# BigDriver.net
KiCad netlist of a schematic drawn in Altium Designer
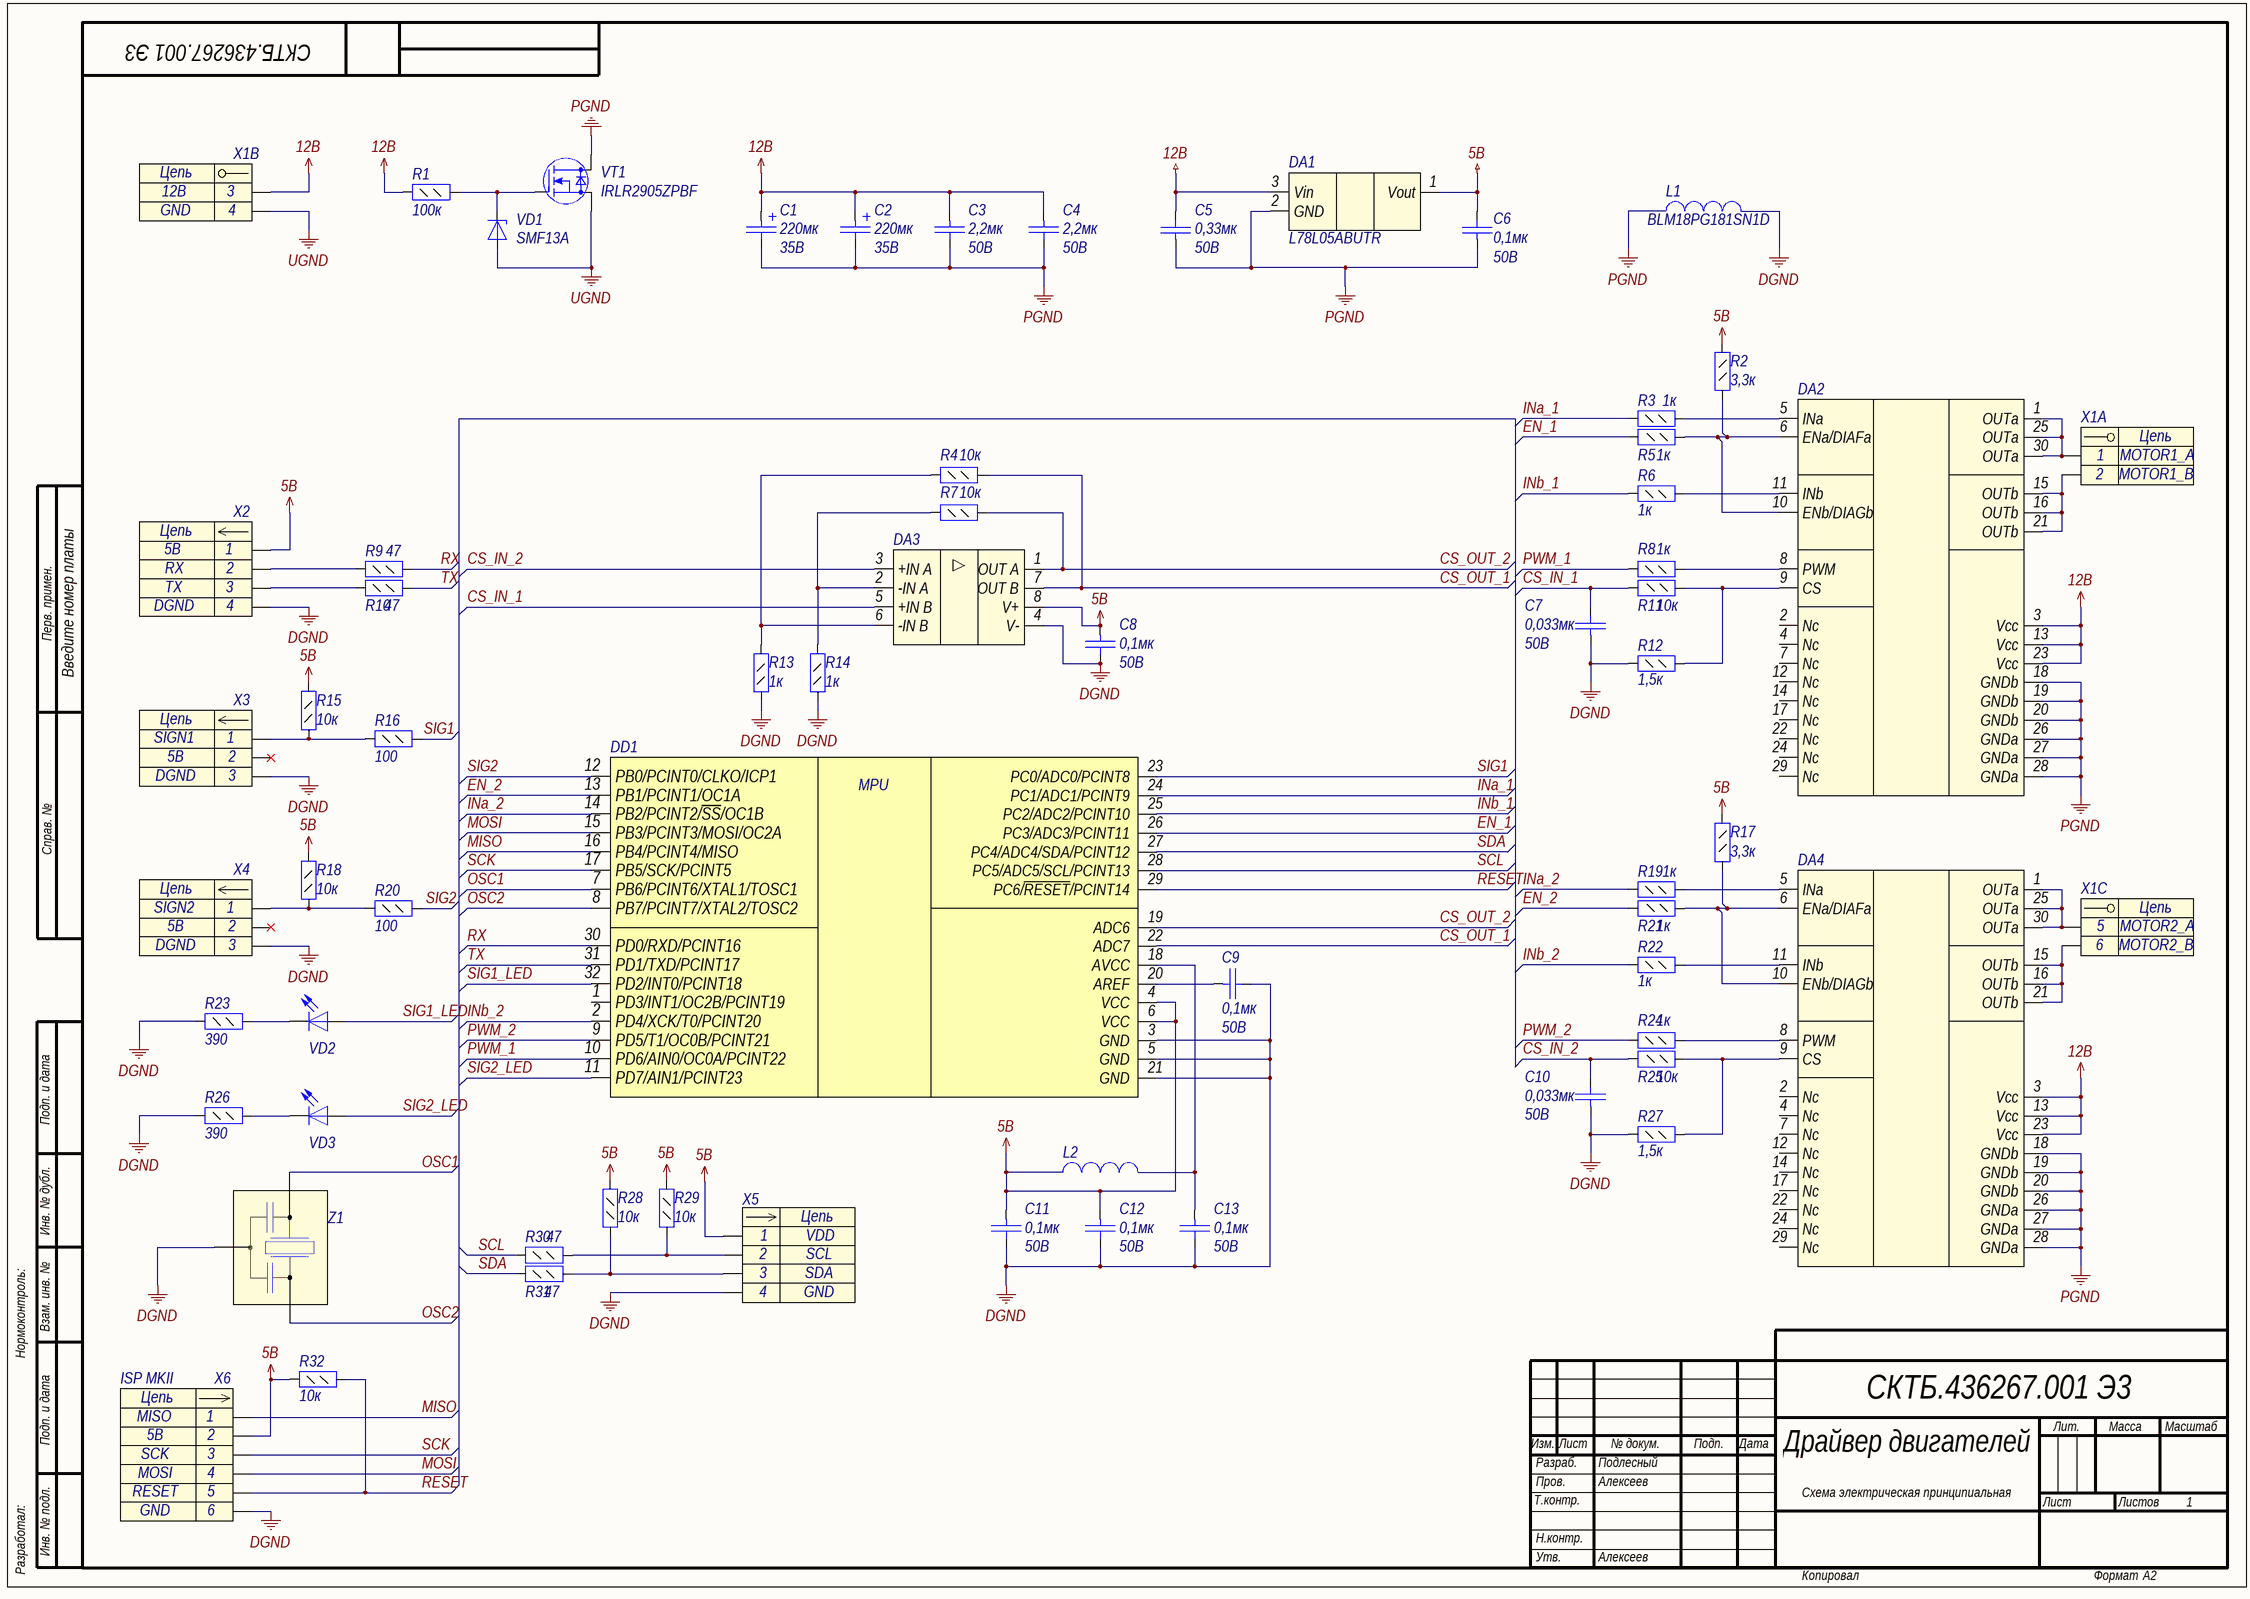
[diagram p0: BigDriver.SchDoc]

(export (version "E")
  (design (tool "Eeschema 10.0.6"))
  (components
    (comp (ref "C1")
      (value "220мк")
      (footprint "k50-35(8x11.5)_MIRROR")
      (description "Конденсатор полярный")
      (fields
        (field (name "VOLTAGE") "35В")
        (field (name "PART NUMBER") "TKR221M1VF11")
        (field (name "Comment") "Capacitor_pol")
      )
      (libsource (lib "MOP44") (part "Capacitor_pol"))
    )
    (comp (ref "C2")
      (value "220мк")
      (footprint "k50-35(8x11.5)_MIRROR")
      (description "Конденсатор полярный")
      (fields
        (field (name "VOLTAGE") "35В")
        (field (name "PART NUMBER") "TKR221M1VF11")
        (field (name "Comment") "Capacitor_pol")
      )
      (libsource (lib "MOP44") (part "Capacitor_pol"))
    )
    (comp (ref "C3")
      (value "2,2мк")
      (footprint "C1206")
      (description "Конденсатор")
      (fields
        (field (name "VOLTAGE") "50В")
        (field (name "PART NUMBER") "GRM31CR71H225KA88**L")
        (field (name "Comment") "Capacitor")
      )
      (libsource (lib "MOP44") (part "Capacitor"))
    )
    (comp (ref "C4")
      (value "2,2мк")
      (footprint "C1206")
      (description "Конденсатор")
      (fields
        (field (name "VOLTAGE") "50В")
        (field (name "PART NUMBER") "GRM31CR71H225KA88**L")
        (field (name "Comment") "Capacitor")
      )
      (libsource (lib "MOP44") (part "Capacitor"))
    )
    (comp (ref "C5")
      (value "0,33мк")
      (footprint "C1206")
      (description "Конденсатор")
      (fields
        (field (name "VOLTAGE") "50В")
        (field (name "PART NUMBER") "GRM319R71H334K")
        (field (name "Comment") "Capacitor")
      )
      (libsource (lib "MOP44") (part "Capacitor"))
    )
    (comp (ref "C6")
      (value "0,1мк")
      (footprint "C0805")
      (description "Конденсатор")
      (fields
        (field (name "VOLTAGE") "50В")
        (field (name "PART NUMBER") "GRM21BR71H104KA01L ")
        (field (name "Comment") "Capacitor")
      )
      (libsource (lib "MOP44") (part "Capacitor"))
    )
    (comp (ref "C7")
      (value "0,033мк")
      (footprint "C1206")
      (description "Конденсатор")
      (fields
        (field (name "VOLTAGE") "50В")
        (field (name "PART NUMBER") "GRM3195C1H333J")
        (field (name "Comment") "Capacitor")
      )
      (libsource (lib "MOP44") (part "Capacitor"))
    )
    (comp (ref "C8")
      (value "0,1мк")
      (footprint "C0805")
      (description "Конденсатор")
      (fields
        (field (name "VOLTAGE") "50В")
        (field (name "PART NUMBER") "GRM216R71H221K")
        (field (name "Comment") "Capacitor")
      )
      (libsource (lib "MOP44") (part "Capacitor"))
    )
    (comp (ref "C9")
      (value "0,1мк")
      (footprint "C0805")
      (description "Конденсатор")
      (fields
        (field (name "VOLTAGE") "50В")
        (field (name "PART NUMBER") "GRM216R71H221K")
        (field (name "Comment") "Capacitor")
      )
      (libsource (lib "MOP44") (part "Capacitor"))
    )
    (comp (ref "C10")
      (value "0,033мк")
      (footprint "C1206")
      (description "Конденсатор")
      (fields
        (field (name "VOLTAGE") "50В")
        (field (name "PART NUMBER") "GRM3195C1H333J")
        (field (name "Comment") "Capacitor")
      )
      (libsource (lib "MOP44") (part "Capacitor"))
    )
    (comp (ref "C11")
      (value "0,1мк")
      (footprint "C0805")
      (description "Конденсатор")
      (fields
        (field (name "VOLTAGE") "50В")
        (field (name "PART NUMBER") "GRM216R71H221K")
        (field (name "Comment") "Capacitor")
      )
      (libsource (lib "MOP44") (part "Capacitor"))
    )
    (comp (ref "C12")
      (value "0,1мк")
      (footprint "C0805")
      (description "Конденсатор")
      (fields
        (field (name "VOLTAGE") "50В")
        (field (name "PART NUMBER") "GRM216R71H221K")
        (field (name "Comment") "Capacitor")
      )
      (libsource (lib "MOP44") (part "Capacitor"))
    )
    (comp (ref "C13")
      (value "0,1мк")
      (footprint "C0805")
      (description "Конденсатор")
      (fields
        (field (name "VOLTAGE") "50В")
        (field (name "PART NUMBER") "GRM216R71H221K")
        (field (name "Comment") "Capacitor")
      )
      (libsource (lib "MOP44") (part "Capacitor"))
    )
    (comp (ref "DA1")
      (value "L78L05ABUTR")
      (footprint "SOT-89-3")
      (description "Cтабилизатор напряжения (+5В; 0.1А), 4%, (-40...+125C)")
      (fields (field (name "MANUFACTURER") "ST Microelectronics"))
      (libsource (lib "MOP44") (part "L78L05ABUTR"))
    )
    (comp (ref "DA2")
      (value "VNH2SP30-E")
      (footprint "MultiPowerSO-30")
      (description "Automotive fully integrated H-bridge motor driver")
      (libsource (lib "MOP44") (part "VNH2SP30-E"))
    )
    (comp (ref "DA3")
      (value "LMV358IDR")
      (footprint "SO8")
      (description "LOW-VOLTAGE RAIL-TO-RAIL OUTPUT OPERATIONAL AMPLIFIERS")
      (libsource (lib "MOP44") (part "LMV358IDR"))
    )
    (comp (ref "DA4")
      (value "VNH2SP30-E")
      (footprint "MultiPowerSO-30")
      (description "Automotive fully integrated H-bridge motor driver")
      (libsource (lib "MOP44") (part "VNH2SP30-E"))
    )
    (comp (ref "DD1")
      (value "ATmega328P-AU")
      (footprint "TQFP-32")
      (description "Микроконтроллер 8-Бит, picoPower, AVR, 20МГц, 32КБ Flash")
      (libsource (lib "MOP44") (part "ATmega328P-AU"))
    )
    (comp (ref "L1")
      (value "Inductor")
      (footprint "L0603")
      (description "EMI Suppression Filter")
      (fields (field (name "PART NUMBER") "BLM18PG181SN1D"))
      (libsource (lib "MOP44") (part "Inductor"))
    )
    (comp (ref "L2")
      (value "Inductor")
      (footprint "L0603")
      (description "EMI Suppression Filter")
      (fields (field (name "PART NUMBER") "BLM18PG181SN1D"))
      (libsource (lib "MOP44") (part "Inductor"))
    )
    (comp (ref "R1")
      (value "100к")
      (footprint "R0805")
      (description "Резистор")
      (fields (field (name "PART NUMBER") "RC0805FR-07100KL") (field (name "POWER") "0,125Вт"))
      (libsource (lib "") (part "Resistor_0,125Вт_1"))
    )
    (comp (ref "R2")
      (value "3,3к")
      (footprint "R0805")
      (description "Резистор")
      (fields (field (name "PART NUMBER") "RC0805FR-0710KL") (field (name "POWER") "0,125Вт"))
      (libsource (lib "") (part "Resistor_0,125Вт_2"))
    )
    (comp (ref "R3")
      (value "1к")
      (footprint "R0805")
      (description "Резистор")
      (fields (field (name "PART NUMBER") "RC0805FR-0710KL") (field (name "POWER") "0,125Вт"))
      (libsource (lib "") (part "Resistor_0,125Вт_1"))
    )
    (comp (ref "R4")
      (value "10к")
      (footprint "R0805")
      (description "Резистор")
      (fields (field (name "PART NUMBER") "RC0805FR-0710KL") (field (name "POWER") "0,125Вт"))
      (libsource (lib "") (part "Resistor_0,125Вт_1"))
    )
    (comp (ref "R5")
      (value "1к")
      (footprint "R0805")
      (description "Резистор")
      (fields (field (name "PART NUMBER") "RC0805FR-0710KL") (field (name "POWER") "0,125Вт"))
      (libsource (lib "MOP44") (part "Resistor_0,125Вт"))
    )
    (comp (ref "R6")
      (value "1к")
      (footprint "R0805")
      (description "Резистор")
      (fields (field (name "PART NUMBER") "RC0805FR-0710KL") (field (name "POWER") "0,125Вт"))
      (libsource (lib "") (part "Resistor_0,125Вт_1"))
    )
    (comp (ref "R7")
      (value "10к")
      (footprint "R0805")
      (description "Резистор")
      (fields (field (name "PART NUMBER") "RC0805FR-0710KL") (field (name "POWER") "0,125Вт"))
      (libsource (lib "") (part "Resistor_0,125Вт_1"))
    )
    (comp (ref "R8")
      (value "1к")
      (footprint "R0805")
      (description "Резистор")
      (fields (field (name "PART NUMBER") "RC0805FR-0710KL") (field (name "POWER") "0,125Вт"))
      (libsource (lib "") (part "Resistor_0,125Вт_1"))
    )
    (comp (ref "R9")
      (value "47")
      (footprint "R0805")
      (description "Резистор")
      (fields (field (name "PART NUMBER") "RC0805FR-0747RL") (field (name "POWER") "0,125Вт"))
      (libsource (lib "") (part "Resistor_0,125Вт_1"))
    )
    (comp (ref "R10")
      (value "47")
      (footprint "R0805")
      (description "Резистор")
      (fields (field (name "PART NUMBER") "RC0805FR-0747RL") (field (name "POWER") "0,125Вт"))
      (libsource (lib "") (part "Resistor_0,125Вт_1"))
    )
    (comp (ref "R11")
      (value "10к")
      (footprint "R0805")
      (description "Резистор")
      (fields (field (name "PART NUMBER") "RC0805FR-0710KL") (field (name "POWER") "0,125Вт"))
      (libsource (lib "MOP44") (part "Resistor_0,125Вт"))
    )
    (comp (ref "R12")
      (value "1,5к")
      (footprint "R0805")
      (description "Резистор")
      (fields (field (name "PART NUMBER") "RC0805FR-0710KL") (field (name "POWER") "0,125Вт"))
      (libsource (lib "") (part "Resistor_0,125Вт_1"))
    )
    (comp (ref "R13")
      (value "1к")
      (footprint "R0805")
      (description "Резистор")
      (fields (field (name "PART NUMBER") "RC0805FR-071KL") (field (name "POWER") "0,125Вт"))
      (libsource (lib "") (part "Resistor_0,125Вт_3"))
    )
    (comp (ref "R14")
      (value "1к")
      (footprint "R0805")
      (description "Резистор")
      (fields (field (name "PART NUMBER") "RC0805FR-071KL") (field (name "POWER") "0,125Вт"))
      (libsource (lib "") (part "Resistor_0,125Вт_3"))
    )
    (comp (ref "R15")
      (value "10к")
      (footprint "R0805")
      (description "Резистор")
      (fields (field (name "PART NUMBER") "RC0805FR-0710KL") (field (name "POWER") "0,125Вт"))
      (libsource (lib "") (part "Resistor_0,125Вт_3"))
    )
    (comp (ref "R16")
      (value "100")
      (footprint "R0805")
      (description "Резистор")
      (fields (field (name "PART NUMBER") "RC0805FR-07100RL") (field (name "POWER") "0,125Вт"))
      (libsource (lib "") (part "Resistor_0,125Вт_1"))
    )
    (comp (ref "R17")
      (value "3,3к")
      (footprint "R0805")
      (description "Резистор")
      (fields (field (name "PART NUMBER") "RC0805FR-0710KL") (field (name "POWER") "0,125Вт"))
      (libsource (lib "") (part "Resistor_0,125Вт_2"))
    )
    (comp (ref "R18")
      (value "10к")
      (footprint "R0805")
      (description "Резистор")
      (fields (field (name "PART NUMBER") "RC0805FR-0710KL") (field (name "POWER") "0,125Вт"))
      (libsource (lib "") (part "Resistor_0,125Вт_3"))
    )
    (comp (ref "R19")
      (value "1к")
      (footprint "R0805")
      (description "Резистор")
      (fields (field (name "PART NUMBER") "RC0805FR-0710KL") (field (name "POWER") "0,125Вт"))
      (libsource (lib "") (part "Resistor_0,125Вт_1"))
    )
    (comp (ref "R20")
      (value "100")
      (footprint "R0805")
      (description "Резистор")
      (fields (field (name "PART NUMBER") "RC0805FR-07100RL") (field (name "POWER") "0,125Вт"))
      (libsource (lib "") (part "Resistor_0,125Вт_1"))
    )
    (comp (ref "R21")
      (value "1к")
      (footprint "R0805")
      (description "Резистор")
      (fields (field (name "PART NUMBER") "RC0805FR-0710KL") (field (name "POWER") "0,125Вт"))
      (libsource (lib "MOP44") (part "Resistor_0,125Вт"))
    )
    (comp (ref "R22")
      (value "1к")
      (footprint "R0805")
      (description "Резистор")
      (fields (field (name "PART NUMBER") "RC0805FR-0710KL") (field (name "POWER") "0,125Вт"))
      (libsource (lib "") (part "Resistor_0,125Вт_1"))
    )
    (comp (ref "R23")
      (value "390")
      (footprint "R0805")
      (description "Резистор")
      (fields (field (name "PART NUMBER") "RC0805FR-07390RL") (field (name "POWER") "0,125Вт"))
      (libsource (lib "") (part "Resistor_0,125Вт_1"))
    )
    (comp (ref "R24")
      (value "1к")
      (footprint "R0805")
      (description "Резистор")
      (fields (field (name "PART NUMBER") "RC0805FR-0710KL") (field (name "POWER") "0,125Вт"))
      (libsource (lib "") (part "Resistor_0,125Вт_1"))
    )
    (comp (ref "R25")
      (value "10к")
      (footprint "R0805")
      (description "Резистор")
      (fields (field (name "PART NUMBER") "RC0805FR-0710KL") (field (name "POWER") "0,125Вт"))
      (libsource (lib "MOP44") (part "Resistor_0,125Вт"))
    )
    (comp (ref "R26")
      (value "390")
      (footprint "R0805")
      (description "Резистор")
      (fields (field (name "PART NUMBER") "RC0805FR-07390RL") (field (name "POWER") "0,125Вт"))
      (libsource (lib "") (part "Resistor_0,125Вт_1"))
    )
    (comp (ref "R27")
      (value "1,5к")
      (footprint "R0805")
      (description "Резистор")
      (fields (field (name "PART NUMBER") "RC0805FR-0710KL") (field (name "POWER") "0,125Вт"))
      (libsource (lib "") (part "Resistor_0,125Вт_1"))
    )
    (comp (ref "R28")
      (value "10к")
      (footprint "R0805")
      (description "Резистор")
      (fields (field (name "PART NUMBER") "RC0805FR-0710KL") (field (name "POWER") "0,125Вт"))
      (libsource (lib "") (part "Resistor_0,125Вт_1"))
    )
    (comp (ref "R29")
      (value "10к")
      (footprint "R0805")
      (description "Резистор")
      (fields (field (name "PART NUMBER") "RC0805FR-0710KL") (field (name "POWER") "0,125Вт"))
      (libsource (lib "") (part "Resistor_0,125Вт_1"))
    )
    (comp (ref "R30")
      (value "47")
      (footprint "R0805")
      (description "Резистор")
      (fields (field (name "PART NUMBER") "RC0805FR-0747RL") (field (name "POWER") "0,125Вт"))
      (libsource (lib "") (part "Resistor_0,125Вт_1"))
    )
    (comp (ref "R31")
      (value "47")
      (footprint "R0805")
      (description "Резистор")
      (fields (field (name "PART NUMBER") "RC0805FR-0747RL") (field (name "POWER") "0,125Вт"))
      (libsource (lib "") (part "Resistor_0,125Вт_1"))
    )
    (comp (ref "R32")
      (value "10к")
      (footprint "R0805")
      (description "Резистор")
      (fields (field (name "PART NUMBER") "RC0805FR-0710KL") (field (name "POWER") "0,125Вт"))
      (libsource (lib "") (part "Resistor_0,125Вт_1"))
    )
    (comp (ref "VD1")
      (value "DiodeZener")
      (footprint "SOD-123")
      (description "Cтабилитрон (лавинный выпрямительный диод) односторонний")
      (fields (field (name "PART NUMBER") "SMF13A"))
      (libsource (lib "MOP44") (part "DiodeZener"))
    )
    (comp (ref "VD2")
      (value "LED")
      (footprint "L_0805")
      (description "Светодиод")
      (fields (field (name "PART NUMBER") "KP-2012EC"))
      (libsource (lib "MOP44") (part "LED"))
    )
    (comp (ref "VD3")
      (value "LED")
      (footprint "L_0805")
      (description "Светодиод")
      (fields (field (name "PART NUMBER") "KP-2012EC"))
      (libsource (lib "MOP44") (part "LED"))
    )
    (comp (ref "VT1")
      (value "N-MOSFET")
      (footprint "DPAK")
      (fields
        (field (name "PART NUMBER") "IRLR2905ZPBF")
        (field (name "MANUFACTURER") "International Rectifier")
      )
      (libsource (lib "MOP44") (part "N-MOSFET"))
    )
    (comp (ref "X1")
      (value "~")
      (footprint "TERMINAL-6WAY-5MM")
      (description "POWER")
      (libsource (lib "") (part "Header_6_motor_1"))
    )
    (comp (ref "X2")
      (value "Header_4_plg")
      (footprint "PLS-4")
      (description "Разъем - 4 конт. вилка")
      (fields (field (name "PART NUMBER") "DS1021-1*4SF112-B"))
      (libsource (lib "") (part "Header_4_plg_1"))
    )
    (comp (ref "X3")
      (value "Header_3_plg")
      (footprint "PLS-3")
      (description "Разъем - 3 конт. вилка")
      (fields (field (name "PART NUMBER") "DS1021-1*3SF112-B"))
      (libsource (lib "MOP44") (part "Header_3_plg"))
    )
    (comp (ref "X4")
      (value "Header_3_plg")
      (footprint "PLS-3")
      (description "Разъем - 3 конт. вилка")
      (fields (field (name "PART NUMBER") "DS1021-1*3SF112-B"))
      (libsource (lib "MOP44") (part "Header_3_plg"))
    )
    (comp (ref "X5")
      (value "Header_4_plg")
      (footprint "PLS-4")
      (description "Разъем - 4 конт. вилка")
      (fields (field (name "PART NUMBER") "DS1021-1*4SF112-B"))
      (libsource (lib "MOP44") (part "Header_4_plg"))
    )
    (comp (ref "X6")
      (value "ISP MKII")
      (footprint "PLS2-6")
      (description "Разъем - 6 конт. вилка")
      (libsource (lib "MOP44") (part "ISP MKII"))
    )
    (comp (ref "Z1")
      (value "QuartzWithCaps")
      (footprint "CSTCE")
      (description "Кварцевый резорнатор со встроенными нагрузочными конденсаторами")
      (fields (field (name "PART NUMBER") "CSTCE12M0G52-R0"))
      (libsource (lib "MOP44") (part "QuartzWithCaps"))
    )
  )
  (nets
    (net (code "1") (name "/CS_IN_1") (class "Default")
      (node (ref "C7") (pin "2") (pinfunction "2_2") (pintype "passive"))
      (node (ref "DA3") (pin "5") (pinfunction "+IN_B_5") (pintype "passive"))
      (node (ref "R11") (pin "2") (pinfunction "2_2") (pintype "passive"))
    )
    (net (code "2") (name "/CS_IN_2") (class "Default")
      (node (ref "C10") (pin "2") (pinfunction "2_2") (pintype "passive"))
      (node (ref "DA3") (pin "3") (pinfunction "+IN_A_3") (pintype "passive"))
      (node (ref "R25") (pin "2") (pinfunction "2_2") (pintype "passive"))
    )
    (net (code "3") (name "/CS_OUT_1") (class "Default")
      (node (ref "DA3") (pin "7") (pinfunction "OUT_B_7") (pintype "passive"))
      (node (ref "DD1") (pin "22") (pinfunction "ADC7_22") (pintype "passive"))
      (node (ref "R4") (pin "2") (pinfunction "2_2") (pintype "passive"))
    )
    (net (code "4") (name "/CS_OUT_2") (class "Default")
      (node (ref "DA3") (pin "1") (pinfunction "OUT_A_1") (pintype "passive"))
      (node (ref "DD1") (pin "19") (pinfunction "ADC6_19") (pintype "passive"))
      (node (ref "R7") (pin "2") (pinfunction "2_2") (pintype "passive"))
    )
    (net (code "5") (name "/EN_1") (class "Default")
      (node (ref "DD1") (pin "26") (pinfunction "PC3/ADC3/PCINT11_26") (pintype "passive"))
      (node (ref "R5") (pin "2") (pinfunction "2_2") (pintype "passive"))
    )
    (net (code "6") (name "/EN_2") (class "Default")
      (node (ref "DD1") (pin "13") (pinfunction "PB1/PCINT1/OC1A_13") (pintype "passive"))
      (node (ref "R21") (pin "2") (pinfunction "2_2") (pintype "passive"))
    )
    (net (code "7") (name "/INa_1") (class "Default")
      (node (ref "DD1") (pin "24") (pinfunction "PC1/ADC1/PCINT9_24") (pintype "passive"))
      (node (ref "R3") (pin "1") (pinfunction "1_1") (pintype "passive"))
    )
    (net (code "8") (name "/INa_2") (class "Default")
      (node (ref "DD1") (pin "14") (pinfunction "PB2/PCINT2/~{SS}/OC1B_14") (pintype "passive"))
      (node (ref "R19") (pin "1") (pinfunction "1_1") (pintype "passive"))
    )
    (net (code "9") (name "/INb_1") (class "Default")
      (node (ref "DD1") (pin "25") (pinfunction "PC2/ADC2/PCINT10_25") (pintype "passive"))
      (node (ref "R6") (pin "1") (pinfunction "1_1") (pintype "passive"))
    )
    (net (code "10") (name "/INb_2") (class "Default")
      (node (ref "DD1") (pin "2") (pinfunction "PD4/XCK/T0/PCINT20_2") (pintype "passive"))
      (node (ref "R22") (pin "1") (pinfunction "1_1") (pintype "passive"))
    )
    (net (code "11") (name "/MISO") (class "Default")
      (node (ref "DD1") (pin "16") (pinfunction "PB4/PCINT4/MISO_16") (pintype "passive"))
      (node (ref "X6") (pin "1") (pinfunction "1_1") (pintype "passive"))
    )
    (net (code "12") (name "/MOSI") (class "Default")
      (node (ref "DD1") (pin "15") (pinfunction "PB3/PCINT3/MOSI/OC2A_15") (pintype "passive"))
      (node (ref "X6") (pin "4") (pinfunction "4_4") (pintype "passive"))
    )
    (net (code "13") (name "/OSC1") (class "Default")
      (node (ref "DD1") (pin "7") (pinfunction "PB6/PCINT6/XTAL1/TOSC1_7") (pintype "passive"))
      (node (ref "Z1") (pin "3") (pinfunction "3_3") (pintype "passive"))
    )
    (net (code "14") (name "/OSC2") (class "Default")
      (node (ref "DD1") (pin "8") (pinfunction "PB7/PCINT7/XTAL2/TOSC2_8") (pintype "passive"))
      (node (ref "Z1") (pin "1") (pinfunction "1_1") (pintype "passive"))
    )
    (net (code "15") (name "/PWM_1") (class "Default")
      (node (ref "DD1") (pin "10") (pinfunction "PD6/AIN0/OC0A/PCINT22_10") (pintype "passive"))
      (node (ref "R8") (pin "1") (pinfunction "1_1") (pintype "passive"))
    )
    (net (code "16") (name "/PWM_2") (class "Default")
      (node (ref "DD1") (pin "9") (pinfunction "PD5/T1/OC0B/PCINT21_9") (pintype "passive"))
      (node (ref "R24") (pin "1") (pinfunction "1_1") (pintype "passive"))
    )
    (net (code "17") (name "/RESET") (class "Default")
      (node (ref "DD1") (pin "29") (pinfunction "PC6/~{RESET}/PCINT14_29") (pintype "passive"))
      (node (ref "R32") (pin "2") (pinfunction "2_2") (pintype "passive"))
      (node (ref "X6") (pin "5") (pinfunction "5_5") (pintype "passive"))
    )
    (net (code "18") (name "/RX") (class "Default")
      (node (ref "DD1") (pin "30") (pinfunction "PD0/RXD/PCINT16_30") (pintype "passive"))
      (node (ref "R9") (pin "2") (pinfunction "2_2") (pintype "passive"))
    )
    (net (code "19") (name "/SCK") (class "Default")
      (node (ref "DD1") (pin "17") (pinfunction "PB5/SCK/PCINT5_17") (pintype "passive"))
      (node (ref "X6") (pin "3") (pinfunction "3_3") (pintype "passive"))
    )
    (net (code "20") (name "/SCL") (class "Default")
      (node (ref "DD1") (pin "28") (pinfunction "PC5/ADC5/SCL/PCINT13_28") (pintype "passive"))
      (node (ref "R30") (pin "1") (pinfunction "1_1") (pintype "passive"))
    )
    (net (code "21") (name "/SDA") (class "Default")
      (node (ref "DD1") (pin "27") (pinfunction "PC4/ADC4/SDA/PCINT12_27") (pintype "passive"))
      (node (ref "R31") (pin "1") (pinfunction "1_1") (pintype "passive"))
    )
    (net (code "22") (name "/SIG1") (class "Default")
      (node (ref "DD1") (pin "23") (pinfunction "PC0/ADC0/PCINT8_23") (pintype "passive"))
      (node (ref "R16") (pin "2") (pinfunction "2_2") (pintype "passive"))
    )
    (net (code "23") (name "/SIG1_LED") (class "Default")
      (node (ref "DD1") (pin "32") (pinfunction "PD2/INT0/PCINT18_32") (pintype "passive"))
      (node (ref "VD2") (pin "2") (pinfunction "A_2") (pintype "passive"))
    )
    (net (code "24") (name "/SIG2") (class "Default")
      (node (ref "DD1") (pin "12") (pinfunction "PB0/PCINT0/CLKO/ICP1_12") (pintype "passive"))
      (node (ref "R20") (pin "2") (pinfunction "2_2") (pintype "passive"))
    )
    (net (code "25") (name "/SIG2_LED") (class "Default")
      (node (ref "DD1") (pin "11") (pinfunction "PD7/AIN1/PCINT23_11") (pintype "passive"))
      (node (ref "VD3") (pin "2") (pinfunction "A_2") (pintype "passive"))
    )
    (net (code "26") (name "/TX") (class "Default")
      (node (ref "DD1") (pin "31") (pinfunction "PD1/TXD/PCINT17_31") (pintype "passive"))
      (node (ref "R10") (pin "2") (pinfunction "2_2") (pintype "passive"))
    )
    (net (code "27") (name "5B") (class "Default")
      (node (ref "C11") (pin "1") (pinfunction "1_1") (pintype "passive"))
      (node (ref "C12") (pin "1") (pinfunction "1_1") (pintype "passive"))
      (node (ref "C6") (pin "2") (pinfunction "2_2") (pintype "passive"))
      (node (ref "C8") (pin "1") (pinfunction "1_1") (pintype "passive"))
      (node (ref "DA1") (pin "1") (pinfunction "Vout_1") (pintype "power_in"))
      (node (ref "DA3") (pin "8") (pinfunction "V+_8") (pintype "passive"))
      (node (ref "DD1") (pin "4") (pinfunction "VCC_4") (pintype "passive"))
      (node (ref "DD1") (pin "6") (pinfunction "VCC_6") (pintype "passive"))
      (node (ref "L2") (pin "1") (pinfunction "1_1") (pintype "passive"))
      (node (ref "R15") (pin "2") (pinfunction "2_2") (pintype "passive"))
      (node (ref "R17") (pin "1") (pinfunction "1_1") (pintype "passive"))
      (node (ref "R18") (pin "2") (pinfunction "2_2") (pintype "passive"))
      (node (ref "R2") (pin "1") (pinfunction "1_1") (pintype "passive"))
      (node (ref "R28") (pin "2") (pinfunction "2_2") (pintype "passive"))
      (node (ref "R29") (pin "2") (pinfunction "2_2") (pintype "passive"))
      (node (ref "R32") (pin "1") (pinfunction "1_1") (pintype "passive"))
      (node (ref "X2") (pin "1") (pinfunction "1_1") (pintype "passive"))
      (node (ref "X5") (pin "1") (pinfunction "1_1") (pintype "passive"))
      (node (ref "X6") (pin "2") (pinfunction "2_2") (pintype "passive"))
    )
    (net (code "28") (name "12B") (class "Default")
      (node (ref "C1") (pin "1") (pinfunction "1_1") (pintype "passive"))
      (node (ref "C2") (pin "1") (pinfunction "1_1") (pintype "passive"))
      (node (ref "C3") (pin "1") (pinfunction "1_1") (pintype "passive"))
      (node (ref "C4") (pin "1") (pinfunction "1_1") (pintype "passive"))
      (node (ref "C5") (pin "2") (pinfunction "2_2") (pintype "passive"))
      (node (ref "DA1") (pin "3") (pinfunction "Vin_3") (pintype "power_in"))
      (node (ref "DA2") (pin "13") (pinfunction "Vcc_13") (pintype "passive"))
      (node (ref "DA2") (pin "23") (pinfunction "Vcc_23") (pintype "passive"))
      (node (ref "DA2") (pin "3") (pinfunction "Vcc_3") (pintype "passive"))
      (node (ref "DA4") (pin "13") (pinfunction "Vcc_13") (pintype "passive"))
      (node (ref "DA4") (pin "23") (pinfunction "Vcc_23") (pintype "passive"))
      (node (ref "DA4") (pin "3") (pinfunction "Vcc_3") (pintype "passive"))
      (node (ref "R1") (pin "1") (pinfunction "1_1") (pintype "passive"))
      (node (ref "X1") (pin "3") (pinfunction "3_3") (pintype "passive"))
    )
    (net (code "29") (name "DGND") (class "Default")
      (node (ref "C10") (pin "1") (pinfunction "1_1") (pintype "passive"))
      (node (ref "C11") (pin "2") (pinfunction "2_2") (pintype "passive"))
      (node (ref "C12") (pin "2") (pinfunction "2_2") (pintype "passive"))
      (node (ref "C13") (pin "2") (pinfunction "2_2") (pintype "passive"))
      (node (ref "C7") (pin "1") (pinfunction "1_1") (pintype "passive"))
      (node (ref "C8") (pin "2") (pinfunction "2_2") (pintype "passive"))
      (node (ref "C9") (pin "2") (pinfunction "2_2") (pintype "passive"))
      (node (ref "DA3") (pin "4") (pinfunction "V-_4") (pintype "passive"))
      (node (ref "DD1") (pin "21") (pinfunction "GND_21") (pintype "passive"))
      (node (ref "DD1") (pin "3") (pinfunction "GND_3") (pintype "passive"))
      (node (ref "DD1") (pin "5") (pinfunction "GND_5") (pintype "passive"))
      (node (ref "L1") (pin "2") (pinfunction "2_2") (pintype "passive"))
      (node (ref "R12") (pin "1") (pinfunction "1_1") (pintype "passive"))
      (node (ref "R13") (pin "1") (pinfunction "1_1") (pintype "passive"))
      (node (ref "R14") (pin "1") (pinfunction "1_1") (pintype "passive"))
      (node (ref "R23") (pin "1") (pinfunction "1_1") (pintype "passive"))
      (node (ref "R26") (pin "1") (pinfunction "1_1") (pintype "passive"))
      (node (ref "R27") (pin "1") (pinfunction "1_1") (pintype "passive"))
      (node (ref "X2") (pin "4") (pinfunction "4_4") (pintype "passive"))
      (node (ref "X3") (pin "3") (pinfunction "3_3") (pintype "passive"))
      (node (ref "X4") (pin "3") (pinfunction "3_3") (pintype "passive"))
      (node (ref "X5") (pin "4") (pinfunction "4_4") (pintype "passive"))
      (node (ref "X6") (pin "6") (pinfunction "6_6") (pintype "passive"))
      (node (ref "Z1") (pin "2") (pinfunction "2_2") (pintype "passive"))
    )
    (net (code "30") (name "Net-(DA2-CS)") (class "Default")
      (node (ref "DA2") (pin "9") (pinfunction "CS_9") (pintype "passive"))
      (node (ref "R11") (pin "1") (pinfunction "1_1") (pintype "passive"))
      (node (ref "R12") (pin "2") (pinfunction "2_2") (pintype "passive"))
    )
    (net (code "31") (name "Net-(DA2-ENa{slash}DIAFa)") (class "Default")
      (node (ref "DA2") (pin "10") (pinfunction "ENb/DIAGb_10") (pintype "passive"))
      (node (ref "DA2") (pin "6") (pinfunction "ENa/DIAFa_6") (pintype "passive"))
      (node (ref "R2") (pin "2") (pinfunction "2_2") (pintype "passive"))
      (node (ref "R5") (pin "1") (pinfunction "1_1") (pintype "passive"))
    )
    (net (code "32") (name "Net-(DA2-INa)") (class "Default")
      (node (ref "DA2") (pin "5") (pinfunction "INa_5") (pintype "passive"))
      (node (ref "R3") (pin "2") (pinfunction "2_2") (pintype "passive"))
    )
    (net (code "33") (name "Net-(DA2-INb)") (class "Default")
      (node (ref "DA2") (pin "11") (pinfunction "INb_11") (pintype "passive"))
      (node (ref "R6") (pin "2") (pinfunction "2_2") (pintype "passive"))
    )
    (net (code "34") (name "Net-(DA2-OUTa-Pad1)") (class "Default")
      (node (ref "DA2") (pin "1") (pinfunction "OUTa_1") (pintype "passive"))
      (node (ref "DA2") (pin "25") (pinfunction "OUTa_25") (pintype "passive"))
      (node (ref "DA2") (pin "30") (pinfunction "OUTa_30") (pintype "passive"))
      (node (ref "X1") (pin "1") (pinfunction "1_1") (pintype "passive"))
    )
    (net (code "35") (name "Net-(DA2-OUTb-Pad15)") (class "Default")
      (node (ref "DA2") (pin "15") (pinfunction "OUTb_15") (pintype "passive"))
      (node (ref "DA2") (pin "16") (pinfunction "OUTb_16") (pintype "passive"))
      (node (ref "DA2") (pin "21") (pinfunction "OUTb_21") (pintype "passive"))
      (node (ref "X1") (pin "2") (pinfunction "2_2") (pintype "passive"))
    )
    (net (code "36") (name "Net-(DA2-PWM)") (class "Default")
      (node (ref "DA2") (pin "8") (pinfunction "PWM_8") (pintype "passive"))
      (node (ref "R8") (pin "2") (pinfunction "2_2") (pintype "passive"))
    )
    (net (code "37") (name "Net-(DA3--IN_A)") (class "Default")
      (node (ref "DA3") (pin "2") (pinfunction "-IN_A_2") (pintype "passive"))
      (node (ref "R14") (pin "2") (pinfunction "2_2") (pintype "passive"))
      (node (ref "R7") (pin "1") (pinfunction "1_1") (pintype "passive"))
    )
    (net (code "38") (name "Net-(DA3--IN_B)") (class "Default")
      (node (ref "DA3") (pin "6") (pinfunction "-IN_B_6") (pintype "passive"))
      (node (ref "R13") (pin "2") (pinfunction "2_2") (pintype "passive"))
      (node (ref "R4") (pin "1") (pinfunction "1_1") (pintype "passive"))
    )
    (net (code "39") (name "Net-(DA4-CS)") (class "Default")
      (node (ref "DA4") (pin "9") (pinfunction "CS_9") (pintype "passive"))
      (node (ref "R25") (pin "1") (pinfunction "1_1") (pintype "passive"))
      (node (ref "R27") (pin "2") (pinfunction "2_2") (pintype "passive"))
    )
    (net (code "40") (name "Net-(DA4-ENa{slash}DIAFa)") (class "Default")
      (node (ref "DA4") (pin "10") (pinfunction "ENb/DIAGb_10") (pintype "passive"))
      (node (ref "DA4") (pin "6") (pinfunction "ENa/DIAFa_6") (pintype "passive"))
      (node (ref "R17") (pin "2") (pinfunction "2_2") (pintype "passive"))
      (node (ref "R21") (pin "1") (pinfunction "1_1") (pintype "passive"))
    )
    (net (code "41") (name "Net-(DA4-INa)") (class "Default")
      (node (ref "DA4") (pin "5") (pinfunction "INa_5") (pintype "passive"))
      (node (ref "R19") (pin "2") (pinfunction "2_2") (pintype "passive"))
    )
    (net (code "42") (name "Net-(DA4-INb)") (class "Default")
      (node (ref "DA4") (pin "11") (pinfunction "INb_11") (pintype "passive"))
      (node (ref "R22") (pin "2") (pinfunction "2_2") (pintype "passive"))
    )
    (net (code "43") (name "Net-(DA4-OUTa-Pad1)") (class "Default")
      (node (ref "DA4") (pin "1") (pinfunction "OUTa_1") (pintype "passive"))
      (node (ref "DA4") (pin "25") (pinfunction "OUTa_25") (pintype "passive"))
      (node (ref "DA4") (pin "30") (pinfunction "OUTa_30") (pintype "passive"))
      (node (ref "X1") (pin "5") (pinfunction "5_5") (pintype "passive"))
    )
    (net (code "44") (name "Net-(DA4-OUTb-Pad15)") (class "Default")
      (node (ref "DA4") (pin "15") (pinfunction "OUTb_15") (pintype "passive"))
      (node (ref "DA4") (pin "16") (pinfunction "OUTb_16") (pintype "passive"))
      (node (ref "DA4") (pin "21") (pinfunction "OUTb_21") (pintype "passive"))
      (node (ref "X1") (pin "6") (pinfunction "6_6") (pintype "passive"))
    )
    (net (code "45") (name "Net-(DA4-PWM)") (class "Default")
      (node (ref "DA4") (pin "8") (pinfunction "PWM_8") (pintype "passive"))
      (node (ref "R24") (pin "2") (pinfunction "2_2") (pintype "passive"))
    )
    (net (code "46") (name "Net-(DD1-AREF)") (class "Default")
      (node (ref "C9") (pin "1") (pinfunction "1_1") (pintype "passive"))
      (node (ref "DD1") (pin "20") (pinfunction "AREF_20") (pintype "passive"))
    )
    (net (code "47") (name "Net-(DD1-AVCC)") (class "Default")
      (node (ref "C13") (pin "1") (pinfunction "1_1") (pintype "passive"))
      (node (ref "DD1") (pin "18") (pinfunction "AVCC_18") (pintype "passive"))
      (node (ref "L2") (pin "2") (pinfunction "2_2") (pintype "passive"))
    )
    (net (code "48") (name "Net-(R9-Pad1)") (class "Default")
      (node (ref "R9") (pin "1") (pinfunction "1_1") (pintype "passive"))
      (node (ref "X2") (pin "2") (pinfunction "2_2") (pintype "passive"))
    )
    (net (code "49") (name "Net-(R10-Pad1)") (class "Default")
      (node (ref "R10") (pin "1") (pinfunction "1_1") (pintype "passive"))
      (node (ref "X2") (pin "3") (pinfunction "3_3") (pintype "passive"))
    )
    (net (code "50") (name "Net-(R15-Pad1)") (class "Default")
      (node (ref "R15") (pin "1") (pinfunction "1_1") (pintype "passive"))
      (node (ref "R16") (pin "1") (pinfunction "1_1") (pintype "passive"))
      (node (ref "X3") (pin "1") (pinfunction "1_1") (pintype "passive"))
    )
    (net (code "51") (name "Net-(R18-Pad1)") (class "Default")
      (node (ref "R18") (pin "1") (pinfunction "1_1") (pintype "passive"))
      (node (ref "R20") (pin "1") (pinfunction "1_1") (pintype "passive"))
      (node (ref "X4") (pin "1") (pinfunction "1_1") (pintype "passive"))
    )
    (net (code "52") (name "Net-(R28-Pad1)") (class "Default")
      (node (ref "R28") (pin "1") (pinfunction "1_1") (pintype "passive"))
      (node (ref "R31") (pin "2") (pinfunction "2_2") (pintype "passive"))
      (node (ref "X5") (pin "3") (pinfunction "3_3") (pintype "passive"))
    )
    (net (code "53") (name "Net-(R29-Pad1)") (class "Default")
      (node (ref "R29") (pin "1") (pinfunction "1_1") (pintype "passive"))
      (node (ref "R30") (pin "2") (pinfunction "2_2") (pintype "passive"))
      (node (ref "X5") (pin "2") (pinfunction "2_2") (pintype "passive"))
    )
    (net (code "54") (name "Net-(VD1-K)") (class "Default")
      (node (ref "R1") (pin "2") (pinfunction "2_2") (pintype "passive"))
      (node (ref "VD1") (pin "1") (pinfunction "K_1") (pintype "passive"))
      (node (ref "VT1") (pin "1") (pinfunction "G_1") (pintype "passive"))
    )
    (net (code "55") (name "Net-(VD2-K)") (class "Default")
      (node (ref "R23") (pin "2") (pinfunction "2_2") (pintype "passive"))
      (node (ref "VD2") (pin "1") (pinfunction "K_1") (pintype "passive"))
    )
    (net (code "56") (name "Net-(VD3-K)") (class "Default")
      (node (ref "R26") (pin "2") (pinfunction "2_2") (pintype "passive"))
      (node (ref "VD3") (pin "1") (pinfunction "K_1") (pintype "passive"))
    )
    (net (code "57") (name "PGND") (class "Default")
      (node (ref "C1") (pin "2") (pinfunction "2_2") (pintype "passive"))
      (node (ref "C2") (pin "2") (pinfunction "2_2") (pintype "passive"))
      (node (ref "C3") (pin "2") (pinfunction "2_2") (pintype "passive"))
      (node (ref "C4") (pin "2") (pinfunction "2_2") (pintype "passive"))
      (node (ref "C5") (pin "1") (pinfunction "1_1") (pintype "passive"))
      (node (ref "C6") (pin "1") (pinfunction "1_1") (pintype "passive"))
      (node (ref "DA1") (pin "2") (pinfunction "GND_2") (pintype "power_in"))
      (node (ref "DA2") (pin "18") (pinfunction "GNDb_18") (pintype "passive"))
      (node (ref "DA2") (pin "19") (pinfunction "GNDb_19") (pintype "passive"))
      (node (ref "DA2") (pin "20") (pinfunction "GNDb_20") (pintype "passive"))
      (node (ref "DA2") (pin "26") (pinfunction "GNDa_26") (pintype "passive"))
      (node (ref "DA2") (pin "27") (pinfunction "GNDa_27") (pintype "passive"))
      (node (ref "DA2") (pin "28") (pinfunction "GNDa_28") (pintype "passive"))
      (node (ref "DA4") (pin "18") (pinfunction "GNDb_18") (pintype "passive"))
      (node (ref "DA4") (pin "19") (pinfunction "GNDb_19") (pintype "passive"))
      (node (ref "DA4") (pin "20") (pinfunction "GNDb_20") (pintype "passive"))
      (node (ref "DA4") (pin "26") (pinfunction "GNDa_26") (pintype "passive"))
      (node (ref "DA4") (pin "27") (pinfunction "GNDa_27") (pintype "passive"))
      (node (ref "DA4") (pin "28") (pinfunction "GNDa_28") (pintype "passive"))
      (node (ref "L1") (pin "1") (pinfunction "1_1") (pintype "passive"))
      (node (ref "VT1") (pin "2") (pinfunction "D_2") (pintype "passive"))
    )
    (net (code "58") (name "UGND") (class "Default")
      (node (ref "VD1") (pin "2") (pinfunction "A_2") (pintype "passive"))
      (node (ref "VT1") (pin "3") (pinfunction "S_3") (pintype "passive"))
      (node (ref "X1") (pin "4") (pinfunction "4_4") (pintype "passive"))
    )
    (net (code "59") (name "unconnected-(DA2-Nc-Pad2)") (class "Default")
      (node (ref "DA2") (pin "2") (pinfunction "Nc_2") (pintype "passive"))
    )
    (net (code "60") (name "unconnected-(DA2-Nc-Pad4)") (class "Default")
      (node (ref "DA2") (pin "4") (pinfunction "Nc_4") (pintype "passive"))
    )
    (net (code "61") (name "unconnected-(DA2-Nc-Pad7)") (class "Default")
      (node (ref "DA2") (pin "7") (pinfunction "Nc_7") (pintype "passive"))
    )
    (net (code "62") (name "unconnected-(DA2-Nc-Pad12)") (class "Default")
      (node (ref "DA2") (pin "12") (pinfunction "Nc_12") (pintype "passive"))
    )
    (net (code "63") (name "unconnected-(DA2-Nc-Pad14)") (class "Default")
      (node (ref "DA2") (pin "14") (pinfunction "Nc_14") (pintype "passive"))
    )
    (net (code "64") (name "unconnected-(DA2-Nc-Pad17)") (class "Default")
      (node (ref "DA2") (pin "17") (pinfunction "Nc_17") (pintype "passive"))
    )
    (net (code "65") (name "unconnected-(DA2-Nc-Pad22)") (class "Default")
      (node (ref "DA2") (pin "22") (pinfunction "Nc_22") (pintype "passive"))
    )
    (net (code "66") (name "unconnected-(DA2-Nc-Pad24)") (class "Default")
      (node (ref "DA2") (pin "24") (pinfunction "Nc_24") (pintype "passive"))
    )
    (net (code "67") (name "unconnected-(DA2-Nc-Pad29)") (class "Default")
      (node (ref "DA2") (pin "29") (pinfunction "Nc_29") (pintype "passive"))
    )
    (net (code "68") (name "unconnected-(DA4-Nc-Pad2)") (class "Default")
      (node (ref "DA4") (pin "2") (pinfunction "Nc_2") (pintype "passive"))
    )
    (net (code "69") (name "unconnected-(DA4-Nc-Pad4)") (class "Default")
      (node (ref "DA4") (pin "4") (pinfunction "Nc_4") (pintype "passive"))
    )
    (net (code "70") (name "unconnected-(DA4-Nc-Pad7)") (class "Default")
      (node (ref "DA4") (pin "7") (pinfunction "Nc_7") (pintype "passive"))
    )
    (net (code "71") (name "unconnected-(DA4-Nc-Pad12)") (class "Default")
      (node (ref "DA4") (pin "12") (pinfunction "Nc_12") (pintype "passive"))
    )
    (net (code "72") (name "unconnected-(DA4-Nc-Pad14)") (class "Default")
      (node (ref "DA4") (pin "14") (pinfunction "Nc_14") (pintype "passive"))
    )
    (net (code "73") (name "unconnected-(DA4-Nc-Pad17)") (class "Default")
      (node (ref "DA4") (pin "17") (pinfunction "Nc_17") (pintype "passive"))
    )
    (net (code "74") (name "unconnected-(DA4-Nc-Pad22)") (class "Default")
      (node (ref "DA4") (pin "22") (pinfunction "Nc_22") (pintype "passive"))
    )
    (net (code "75") (name "unconnected-(DA4-Nc-Pad24)") (class "Default")
      (node (ref "DA4") (pin "24") (pinfunction "Nc_24") (pintype "passive"))
    )
    (net (code "76") (name "unconnected-(DA4-Nc-Pad29)") (class "Default")
      (node (ref "DA4") (pin "29") (pinfunction "Nc_29") (pintype "passive"))
    )
    (net (code "77") (name "unconnected-(DD1-PD3{slash}INT1{slash}OC2B{slash}PCINT19-Pad1)") (class "Default")
      (node (ref "DD1") (pin "1") (pinfunction "PD3/INT1/OC2B/PCINT19_1") (pintype "passive"))
    )
    (net (code "78") (name "unconnected-(X3-Pad2)") (class "Default")
      (node (ref "X3") (pin "2") (pinfunction "2_2") (pintype "passive+no_connect"))
    )
    (net (code "79") (name "unconnected-(X4-Pad2)") (class "Default")
      (node (ref "X4") (pin "2") (pinfunction "2_2") (pintype "passive+no_connect"))
    )
  )
)
